# AL4_Signal_Isolation.net
KiCad netlist of a schematic drawn in Altium Designer
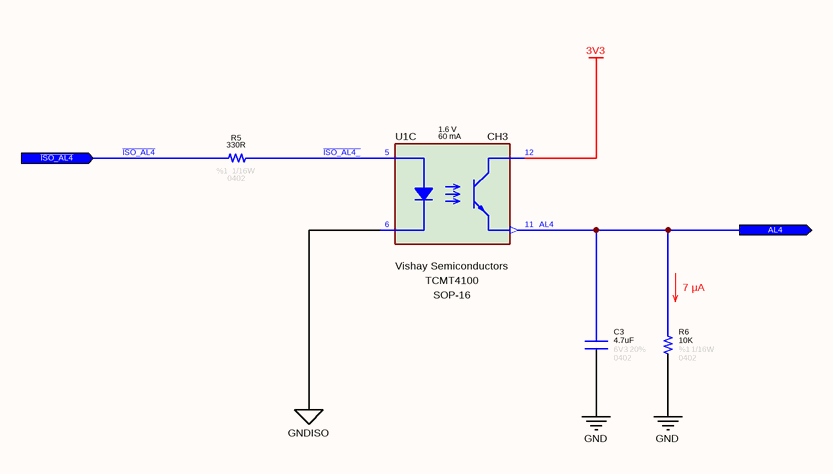
[diagram p0: AL4 Signal Isolation.SchDoc]

(export (version "E")
  (design (tool "Eeschema 10.0.6"))
  (components
    (comp (ref "C3")
      (value "4.7uF")
      (footprint "CAPACITOR_0402")
      (description "Multilayer Ceramic Capacitors - SMD - 6V3 4.7uF X5R 0402 20%")
      (fields
        (field (name "MANUFACTURER PART NUMBER") "C0402C475M9PACTU")
        (field (name "TOLERANCE") "20%")
        (field (name "CASE") "0402")
        (field (name "VOLTAGE") "6V3")
        (field (name "Comment") "Capacitor - 4.7uF [0402] (Ceramic)")
      )
      (libsource (lib "Akkoyun") (part "Capacitor - 4.7uF [0402-6V3]"))
    )
    (comp (ref "R5")
      (value "330R")
      (footprint "RESISTOR_0402")
      (description "Thick Film Resistors - SMD 1/16 W 330 Ohm 1%")
      (fields
        (field (name "MANUFACTURER PART NUMBER") "CRCW0402330RFKED")
        (field (name "CASE") "0402")
        (field (name "TOLERANCE") "%1")
        (field (name "POWER") "1/16W")
        (field (name "Comment") "330R - 0402 - %1 - 1/16W")
      )
      (libsource (lib "Akkoyun") (part "Resistor - 330R [0402]"))
    )
    (comp (ref "R6")
      (value "10K")
      (footprint "RESISTOR_0402")
      (description "Thick Film Resistors - SMD 1/16 W 10 KOhm 1%")
      (fields
        (field (name "MANUFACTURER PART NUMBER") "CRCW040210K0FKED")
        (field (name "TOLERANCE") "%1")
        (field (name "CASE") "0402")
        (field (name "POWER") "1/16W")
        (field (name "Comment") "10K - 0402 - %1 - 1/16W")
      )
      (libsource (lib "Akkoyun") (part "Resistor - 10K [0402]"))
    )
    (comp (ref "U1")
      (value "TCMT4100")
      (footprint "SO-16")
      (description "OptpCoupler 4CH 16 Pin (SOP16)")
      (fields
        (field (name "IF - FORWARD CURRENT") "60 mA")
        (field (name "VF - FORWARD VOLTAGE") "1.6 V")
        (field (name "MANUFACTURER NAME") "Vishay Semiconductors")
        (field (name "MANUFACTURER PART NUMBER") "TCMT4100")
        (field (name "CASE") "SOP-16")
      )
      (libsource (lib "Akkoyun") (part "IC - TCMT4100"))
    )
  )
  (nets
    (net (code "1") (name "/AL4") (class "Default")
      (node (ref "C3") (pin "2") (pinfunction "2_2") (pintype "passive"))
      (node (ref "R6") (pin "2") (pinfunction "2_2") (pintype "passive"))
      (node (ref "U1") (pin "11") (pinfunction "Emiter_CH3_11") (pintype "output"))
    )
    (net (code "2") (name "/~{ISO_AL4_}") (class "Default")
      (node (ref "R5") (pin "1") (pinfunction "1_1") (pintype "passive"))
      (node (ref "U1") (pin "5") (pinfunction "Anode_CH3_5") (pintype "passive"))
    )
    (net (code "3") (name "/~{ISO_AL4}") (class "Default")
      (node (ref "R5") (pin "2") (pinfunction "2_2") (pintype "passive"))
    )
    (net (code "4") (name "3V3") (class "Default")
      (node (ref "U1") (pin "12") (pinfunction "Collector_CH3_12") (pintype "passive"))
    )
    (net (code "5") (name "GND") (class "Default")
      (node (ref "C3") (pin "1") (pinfunction "1_1") (pintype "passive"))
      (node (ref "R6") (pin "1") (pinfunction "1_1") (pintype "passive"))
    )
    (net (code "6") (name "GNDISO") (class "Default")
      (node (ref "U1") (pin "6") (pinfunction "Cathode_CH3_6") (pintype "passive"))
    )
  )
)
